# SCH.net
KiCad netlist of a schematic drawn in EasyEDA
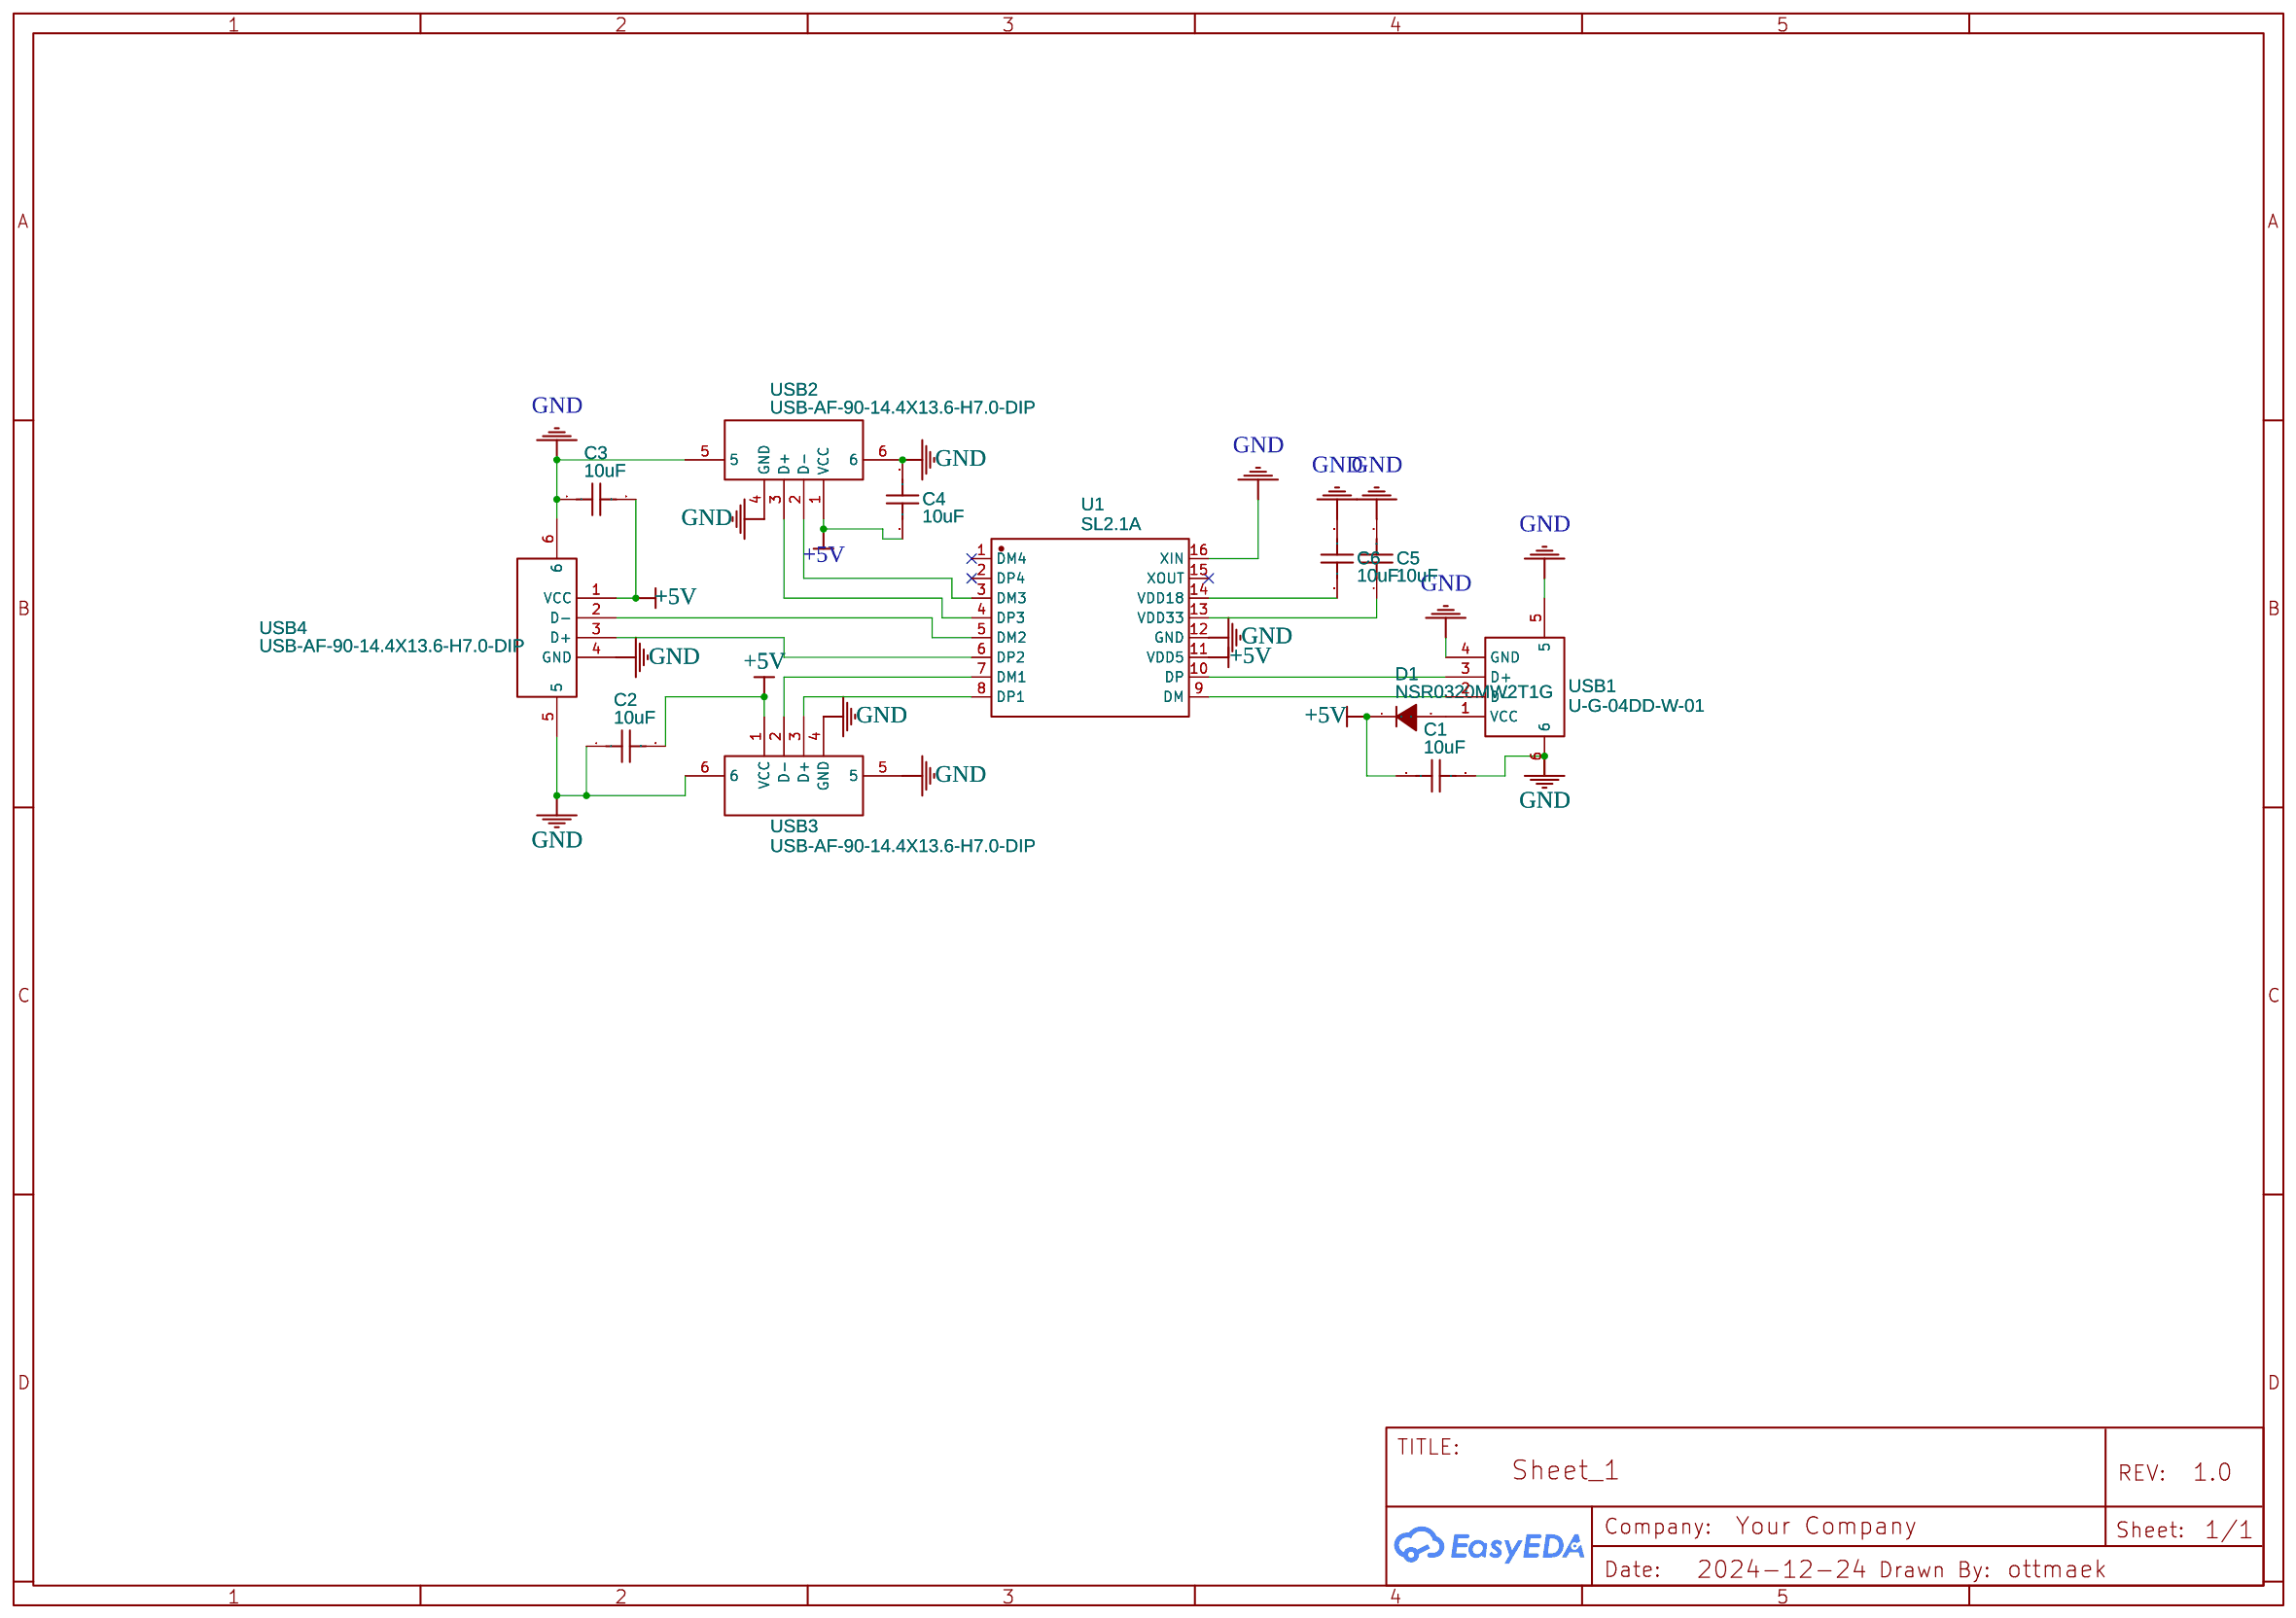
[diagram p0: schematic sheet]

(export (version "E")
  (design (tool "Eeschema 10.0.6"))
  (components
    (comp (ref "C1")
      (value "10uF")
      (fields
        (field (name "Manufacturer Part") "CL10A106KP8NNNC")
        (field (name "Manufacturer") "SAMSUNG(三星)")
      )
      (libsource (lib "") (part "CL10A106KP8NNNC_1"))
    )
    (comp (ref "C2")
      (value "10uF")
      (fields
        (field (name "Manufacturer Part") "CL10A106KP8NNNC")
        (field (name "Manufacturer") "SAMSUNG(三星)")
      )
      (libsource (lib "") (part "CL10A106KP8NNNC_1"))
    )
    (comp (ref "C3")
      (value "10uF")
      (fields
        (field (name "Manufacturer Part") "CL10A106KP8NNNC")
        (field (name "Manufacturer") "SAMSUNG(三星)")
      )
      (libsource (lib "") (part "CL10A106KP8NNNC_1"))
    )
    (comp (ref "C4")
      (value "10uF")
      (fields
        (field (name "Manufacturer Part") "CL10A106KP8NNNC")
        (field (name "Manufacturer") "SAMSUNG(三星)")
      )
      (libsource (lib "") (part "CL10A106KP8NNNC"))
    )
    (comp (ref "C5")
      (value "10uF")
      (fields
        (field (name "Manufacturer Part") "CL10A106KP8NNNC")
        (field (name "Manufacturer") "SAMSUNG(三星)")
      )
      (libsource (lib "") (part "CL10A106KP8NNNC"))
    )
    (comp (ref "C6")
      (value "10uF")
      (fields
        (field (name "Manufacturer Part") "CL10A106KP8NNNC")
        (field (name "Manufacturer") "SAMSUNG(三星)")
      )
      (libsource (lib "") (part "CL10A106KP8NNNC"))
    )
    (comp (ref "D1")
      (value "NSR0320MW2T1G")
      (fields (field (name "Manufacturer") "onsemi(安森美)"))
      (libsource (lib "") (part "NSR0320MW2T1G"))
    )
    (comp (ref "U1")
      (value "SL2.1A")
      (fields (field (name "Manufacturer") "CoreChips(和芯润德)"))
      (libsource (lib "") (part "SL2.1A"))
    )
    (comp (ref "USB1")
      (value "U-G-04DD-W-01")
      (fields (field (name "Manufacturer Part") "U-G-O4DD-W-1") (field (name "Manufacturer") "韩国韩荣"))
      (libsource (lib "") (part "U-G-04DD-W-01"))
    )
    (comp (ref "USB2")
      (value "USB-AF-90-14.4X13.6-H7.0-DIP")
      (fields (field (name "Manufacturer Part") "903-131A1011D10100") (field (name "Manufacturer") "精拓金"))
      (libsource (lib "") (part "USB-AF-90-14.4X13.6-H7.0-DIP_2"))
    )
    (comp (ref "USB3")
      (value "USB-AF-90-14.4X13.6-H7.0-DIP")
      (fields (field (name "Manufacturer Part") "903-131A1011D10100") (field (name "Manufacturer") "精拓金"))
      (libsource (lib "") (part "USB-AF-90-14.4X13.6-H7.0-DIP"))
    )
    (comp (ref "USB4")
      (value "USB-AF-90-14.4X13.6-H7.0-DIP")
      (fields (field (name "Manufacturer Part") "903-131A1011D10100") (field (name "Manufacturer") "精拓金"))
      (libsource (lib "") (part "USB-AF-90-14.4X13.6-H7.0-DIP_1"))
    )
  )
  (nets
    (net (code "1") (name "+5V") (class "Default")
      (node (ref "C1") (pin "1") (pinfunction "1_1") (pintype "unspecified"))
      (node (ref "C2") (pin "2") (pinfunction "2_2") (pintype "unspecified"))
      (node (ref "C3") (pin "2") (pinfunction "2_2") (pintype "unspecified"))
      (node (ref "C4") (pin "1") (pinfunction "1_1") (pintype "unspecified"))
      (node (ref "D1") (pin "1") (pinfunction "C_1") (pintype "unspecified"))
      (node (ref "U1") (pin "11") (pinfunction "VDD5_11") (pintype "unspecified"))
      (node (ref "USB2") (pin "1") (pinfunction "VCC_1") (pintype "unspecified"))
      (node (ref "USB3") (pin "1") (pinfunction "VCC_1") (pintype "unspecified"))
      (node (ref "USB4") (pin "1") (pinfunction "VCC_1") (pintype "unspecified"))
    )
    (net (code "2") (name "GND") (class "Default")
      (node (ref "C1") (pin "2") (pinfunction "2_2") (pintype "unspecified"))
      (node (ref "C2") (pin "1") (pinfunction "1_1") (pintype "unspecified"))
      (node (ref "C3") (pin "1") (pinfunction "1_1") (pintype "unspecified"))
      (node (ref "C4") (pin "2") (pinfunction "2_2") (pintype "unspecified"))
      (node (ref "C5") (pin "2") (pinfunction "2_2") (pintype "unspecified"))
      (node (ref "C6") (pin "2") (pinfunction "2_2") (pintype "unspecified"))
      (node (ref "U1") (pin "12") (pinfunction "GND_12") (pintype "unspecified"))
      (node (ref "U1") (pin "16") (pinfunction "XIN_16") (pintype "unspecified"))
      (node (ref "USB1") (pin "4") (pinfunction "GND_4") (pintype "unspecified"))
      (node (ref "USB1") (pin "5") (pinfunction "5_5") (pintype "unspecified"))
      (node (ref "USB1") (pin "6") (pinfunction "6_6") (pintype "unspecified"))
      (node (ref "USB2") (pin "4") (pinfunction "GND_4") (pintype "unspecified"))
      (node (ref "USB2") (pin "5") (pinfunction "5_5") (pintype "unspecified"))
      (node (ref "USB2") (pin "6") (pinfunction "6_6") (pintype "unspecified"))
      (node (ref "USB3") (pin "4") (pinfunction "GND_4") (pintype "unspecified"))
      (node (ref "USB3") (pin "5") (pinfunction "5_5") (pintype "unspecified"))
      (node (ref "USB3") (pin "6") (pinfunction "6_6") (pintype "unspecified"))
      (node (ref "USB4") (pin "4") (pinfunction "GND_4") (pintype "unspecified"))
      (node (ref "USB4") (pin "5") (pinfunction "5_5") (pintype "unspecified"))
      (node (ref "USB4") (pin "6") (pinfunction "6_6") (pintype "unspecified"))
    )
    (net (code "3") (name "Net-(D1-A)") (class "Default")
      (node (ref "D1") (pin "2") (pinfunction "A_2") (pintype "unspecified"))
      (node (ref "USB1") (pin "1") (pinfunction "VCC_1") (pintype "unspecified"))
    )
    (net (code "4") (name "Net-(U1-DM)") (class "Default")
      (node (ref "U1") (pin "9") (pinfunction "DM_9") (pintype "unspecified"))
      (node (ref "USB1") (pin "2") (pinfunction "D-_2") (pintype "unspecified"))
    )
    (net (code "5") (name "Net-(U1-DM1)") (class "Default")
      (node (ref "U1") (pin "7") (pinfunction "DM1_7") (pintype "unspecified"))
      (node (ref "USB3") (pin "2") (pinfunction "D-_2") (pintype "unspecified"))
    )
    (net (code "6") (name "Net-(U1-DM2)") (class "Default")
      (node (ref "U1") (pin "5") (pinfunction "DM2_5") (pintype "unspecified"))
      (node (ref "USB4") (pin "2") (pinfunction "D-_2") (pintype "unspecified"))
    )
    (net (code "7") (name "Net-(U1-DM3)") (class "Default")
      (node (ref "U1") (pin "3") (pinfunction "DM3_3") (pintype "unspecified"))
      (node (ref "USB2") (pin "2") (pinfunction "D-_2") (pintype "unspecified"))
    )
    (net (code "8") (name "Net-(U1-DP)") (class "Default")
      (node (ref "U1") (pin "10") (pinfunction "DP_10") (pintype "unspecified"))
      (node (ref "USB1") (pin "3") (pinfunction "D+_3") (pintype "unspecified"))
    )
    (net (code "9") (name "Net-(U1-DP1)") (class "Default")
      (node (ref "U1") (pin "8") (pinfunction "DP1_8") (pintype "unspecified"))
      (node (ref "USB3") (pin "3") (pinfunction "D+_3") (pintype "unspecified"))
    )
    (net (code "10") (name "Net-(U1-DP2)") (class "Default")
      (node (ref "U1") (pin "6") (pinfunction "DP2_6") (pintype "unspecified"))
      (node (ref "USB4") (pin "3") (pinfunction "D+_3") (pintype "unspecified"))
    )
    (net (code "11") (name "Net-(U1-DP3)") (class "Default")
      (node (ref "U1") (pin "4") (pinfunction "DP3_4") (pintype "unspecified"))
      (node (ref "USB2") (pin "3") (pinfunction "D+_3") (pintype "unspecified"))
    )
    (net (code "12") (name "Net-(U1-VDD18)") (class "Default")
      (node (ref "C6") (pin "1") (pinfunction "1_1") (pintype "unspecified"))
      (node (ref "U1") (pin "14") (pinfunction "VDD18_14") (pintype "unspecified"))
    )
    (net (code "13") (name "Net-(U1-VDD33)") (class "Default")
      (node (ref "C5") (pin "1") (pinfunction "1_1") (pintype "unspecified"))
      (node (ref "U1") (pin "13") (pinfunction "VDD33_13") (pintype "unspecified"))
    )
    (net (code "14") (name "unconnected-(U1-DM4-Pad1)") (class "Default")
      (node (ref "U1") (pin "1") (pinfunction "DM4_1") (pintype "unspecified+no_connect"))
    )
    (net (code "15") (name "unconnected-(U1-DP4-Pad2)") (class "Default")
      (node (ref "U1") (pin "2") (pinfunction "DP4_2") (pintype "unspecified+no_connect"))
    )
    (net (code "16") (name "unconnected-(U1-XOUT-Pad15)") (class "Default")
      (node (ref "U1") (pin "15") (pinfunction "XOUT_15") (pintype "unspecified+no_connect"))
    )
  )
)
